# Sheet1.net
KiCad netlist of a schematic drawn in Altium Designer
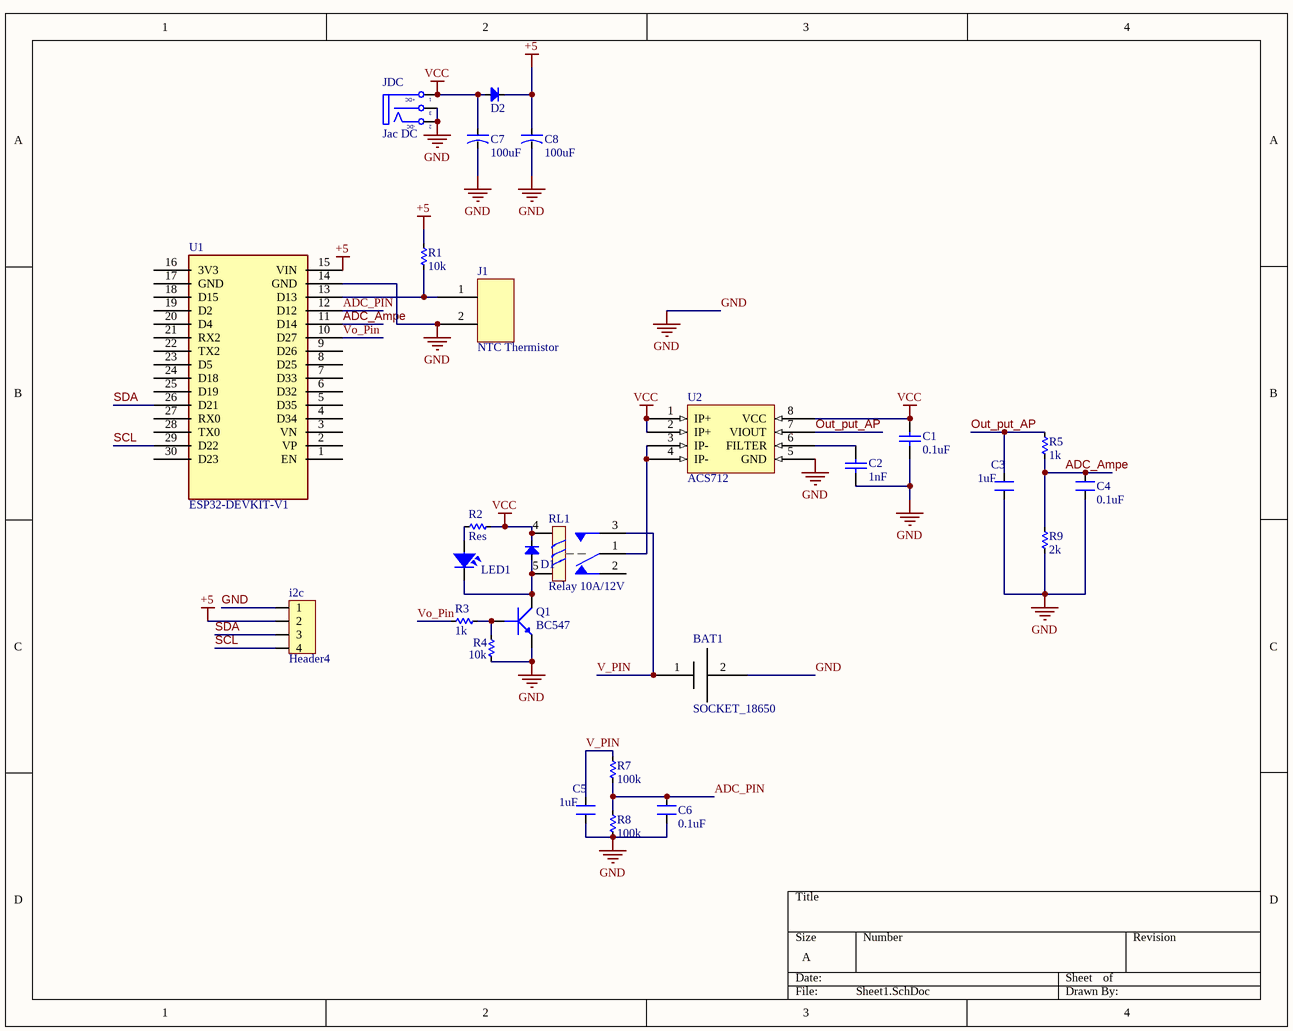
[diagram p0: Sheet1.SchDoc]

(export (version "E")
  (design (tool "Eeschema 10.0.6"))
  (components
    (comp (ref "BAT1")
      (value "SOCKET_18650")
      (footprint "SOCKET_18650_1PIN")
      (libsource (lib "Integrated_Library1") (part "SOCKET_18650_1PIN"))
    )
    (comp (ref "C1")
      (value "0.1uF")
      (footprint "CAPC_0603_N")
      (description "CAP CER 0.1UF 50V X7R 0603")
      (fields (field (name "PARTNUMBER") "C0603X7R104K500NT") (field (name "CREATOR") "ThangND"))
      (libsource (lib "MKP_lib") (part "CAP"))
    )
    (comp (ref "C2")
      (value "1nF")
      (footprint "CAPC_0603_N")
      (description "CAP CER 0.1UF 50V X7R 0603")
      (fields (field (name "PARTNUMBER") "C0603X7R104K500NT") (field (name "CREATOR") "ThangND"))
      (libsource (lib "MKP_lib") (part "CAP"))
    )
    (comp (ref "C3")
      (value "1uF")
      (footprint "CN1")
      (description "Cap np  1pF - 472pF")
      (libsource (lib "syhaunguyen") (part "CN1"))
    )
    (comp (ref "C4")
      (value "0.1uF")
      (footprint "CN1")
      (description "Cap np  1pF - 472pF")
      (libsource (lib "syhaunguyen") (part "CN1"))
    )
    (comp (ref "C5")
      (value "1uF")
      (footprint "CN1")
      (description "Cap np  1pF - 472pF")
      (libsource (lib "syhaunguyen") (part "CN1"))
    )
    (comp (ref "C6")
      (value "0.1uF")
      (footprint "CN1")
      (description "Cap np  1pF - 472pF")
      (libsource (lib "syhaunguyen") (part "CN1"))
    )
    (comp (ref "C7")
      (value "100uF")
      (footprint "CA-ALU-6.3")
      (description "Capacitor (Semiconductor SIM Model)")
      (fields (field (name "PUBLISHER") "Altium Limited"))
      (libsource (lib "LIBRARY") (part "CN-ALU-DIP"))
    )
    (comp (ref "C8")
      (value "100uF")
      (footprint "CA-ALU-6.3")
      (description "Capacitor (Semiconductor SIM Model)")
      (fields (field (name "PUBLISHER") "Altium Limited"))
      (libsource (lib "LIBRARY") (part "CN-ALU-DIP"))
    )
    (comp (ref "D1")
      (value "Diode")
      (footprint "DIO-1A")
      (description "Default Diode")
      (fields (field (name "PUBLISHER") "Altium Limited"))
      (libsource (lib "LIBRARY") (part "Diode"))
    )
    (comp (ref "D2")
      (value "Diode")
      (footprint "DIO-1A")
      (description "Default Diode")
      (fields (field (name "PUBLISHER") "Altium Limited"))
      (libsource (lib "LIBRARY") (part "Diode"))
    )
    (comp (ref "i2c")
      (value "Header4")
      (footprint "Header4")
      (description "Header IDC, 4 x 1 Pin Vertical 2.54mm Pitch (Non-Boxed, Male)")
      (fields
        (field (name "MANUFACTURER") "Würth Elektronik eiSos GmbH")
        (field (name "PARTNO") "613002143121")
        (field (name "CREATED BY") "Karrer Zheng")
      )
      (libsource (lib "LIBRARY") (part "Header4"))
    )
    (comp (ref "J1")
      (value "NTC Thermistor")
      (footprint "NTC Thermistor")
      (libsource (lib "Hainv-makipos") (part "NTC Thermistor"))
    )
    (comp (ref "JDC")
      (value "Jac DC")
      (footprint "DC0")
      (description "Jac DC input")
      (libsource (lib "LIBRARY") (part "DCIN"))
    )
    (comp (ref "LED1")
      (value "LED")
      (footprint "LED-5-Green")
      (description "LED Single colour Green and Red")
      (libsource (lib "LIBRARY") (part "LED"))
    )
    (comp (ref "Q1")
      (value "BC547")
      (footprint "TO-92")
      (description "Transistors - BJT NPN 45V 100mA")
      (libsource (lib "MHieuLib") (part "BC547"))
    )
    (comp (ref "R1")
      (value "10k")
      (footprint "RES-1/4W")
      (description "Res")
      (fields
        (field (name "MANUFACTURER") "Generic Components")
        (field (name "PUBLISHER") "Altium Hobart Technology Centre")
      )
      (libsource (lib "LIBRARY") (part "Res"))
    )
    (comp (ref "R2")
      (value "Res")
      (footprint "RES-1/4W")
      (fields
        (field (name "MANUFACTURER") "Generic Components")
        (field (name "PUBLISHER") "Altium Hobart Technology Centre")
      )
      (libsource (lib "LIBRARY") (part "Res"))
    )
    (comp (ref "R3")
      (value "1k")
      (footprint "RES-1/4W")
      (description "Res")
      (fields
        (field (name "MANUFACTURER") "Generic Components")
        (field (name "PUBLISHER") "Altium Hobart Technology Centre")
      )
      (libsource (lib "LIBRARY") (part "Res"))
    )
    (comp (ref "R4")
      (value "10k")
      (footprint "RES-1/4W")
      (description "Res")
      (fields
        (field (name "MANUFACTURER") "Generic Components")
        (field (name "PUBLISHER") "Altium Hobart Technology Centre")
      )
      (libsource (lib "LIBRARY") (part "Res"))
    )
    (comp (ref "R5")
      (value "1k")
      (footprint "RES-1/4W")
      (description "Res")
      (fields
        (field (name "MANUFACTURER") "Generic Components")
        (field (name "PUBLISHER") "Altium Hobart Technology Centre")
      )
      (libsource (lib "LIBRARY") (part "Res"))
    )
    (comp (ref "R7")
      (value "100k")
      (footprint "RES-1/4W")
      (description "Res")
      (fields
        (field (name "MANUFACTURER") "Generic Components")
        (field (name "PUBLISHER") "Altium Hobart Technology Centre")
      )
      (libsource (lib "LIBRARY") (part "Res"))
    )
    (comp (ref "R8")
      (value "100k")
      (footprint "RES-1/4W")
      (description "Res")
      (fields
        (field (name "MANUFACTURER") "Generic Components")
        (field (name "PUBLISHER") "Altium Hobart Technology Centre")
      )
      (libsource (lib "LIBRARY") (part "Res"))
    )
    (comp (ref "R9")
      (value "2k")
      (footprint "RES-1/4W")
      (description "Res")
      (fields
        (field (name "MANUFACTURER") "Generic Components")
        (field (name "PUBLISHER") "Altium Hobart Technology Centre")
      )
      (libsource (lib "LIBRARY") (part "Res"))
    )
    (comp (ref "RL1")
      (value "Relay 10A/12V")
      (footprint "RELAY 5")
      (description "Relay SPDT,10A - 12VDC 5 Pin")
      (libsource (lib "LIBRARY") (part "Relay 5"))
    )
    (comp (ref "U1")
      (value "ESP32-DEVKIT-V1")
      (footprint "ESP32-DEVKIT-V1")
      (description "ESP32-DEVKIT-V1 30Pin")
      (libsource (lib "Library") (part "ESP32-DEVKIT-V1"))
    )
    (comp (ref "U2")
      (value "ACS712")
      (footprint "ACS712")
      (description "5A SOIC-8 Current Sensors ROHS")
      (libsource (lib "Hainv-makipos") (part "ACS712"))
    )
  )
  (nets
    (net (code "1") (name "+5") (class "Default")
      (node (ref "C8") (pin "1") (pinfunction "1_1") (pintype "passive"))
      (node (ref "D2") (pin "2") (pinfunction "K_2") (pintype "passive"))
      (node (ref "R1") (pin "2") (pinfunction "2_2") (pintype "passive"))
      (node (ref "U1") (pin "15") (pinfunction "VIN_15") (pintype "passive"))
      (node (ref "i2c") (pin "2") (pinfunction "2_2") (pintype "passive"))
    )
    (net (code "2") (name "/ADC_Ampe") (class "Default")
      (node (ref "C4") (pin "2") (pinfunction "2_2") (pintype "passive"))
      (node (ref "R5") (pin "1") (pinfunction "1_1") (pintype "passive"))
      (node (ref "R9") (pin "2") (pinfunction "2_2") (pintype "passive"))
      (node (ref "U1") (pin "11") (pinfunction "D14_11") (pintype "passive"))
    )
    (net (code "3") (name "/ADC_PIN") (class "Default")
      (node (ref "C6") (pin "2") (pinfunction "2_2") (pintype "passive"))
      (node (ref "R7") (pin "1") (pinfunction "1_1") (pintype "passive"))
      (node (ref "R8") (pin "2") (pinfunction "2_2") (pintype "passive"))
      (node (ref "U1") (pin "12") (pinfunction "D12_12") (pintype "passive"))
    )
    (net (code "4") (name "/Out_put_AP") (class "Default")
      (node (ref "C3") (pin "2") (pinfunction "2_2") (pintype "passive"))
      (node (ref "R5") (pin "2") (pinfunction "2_2") (pintype "passive"))
      (node (ref "U2") (pin "7") (pinfunction "VIOUT_7") (pintype "input"))
    )
    (net (code "5") (name "/SCL") (class "Default")
      (node (ref "U1") (pin "29") (pinfunction "D22_29") (pintype "passive"))
      (node (ref "i2c") (pin "4") (pinfunction "4_4") (pintype "passive"))
    )
    (net (code "6") (name "/SDA") (class "Default")
      (node (ref "U1") (pin "26") (pinfunction "D21_26") (pintype "passive"))
      (node (ref "i2c") (pin "3") (pinfunction "3_3") (pintype "passive"))
    )
    (net (code "7") (name "/V_PIN") (class "Default")
      (node (ref "BAT1") (pin "1") (pinfunction "VCC_1") (pintype "passive"))
      (node (ref "C5") (pin "2") (pinfunction "2_2") (pintype "passive"))
      (node (ref "R7") (pin "2") (pinfunction "2_2") (pintype "passive"))
      (node (ref "RL1") (pin "3") (pinfunction "3_3") (pintype "passive"))
    )
    (net (code "8") (name "/Vo_Pin") (class "Default")
      (node (ref "R3") (pin "2") (pinfunction "2_2") (pintype "passive"))
      (node (ref "U1") (pin "10") (pinfunction "D27_10") (pintype "passive"))
    )
    (net (code "9") (name "GND") (class "Default")
      (node (ref "BAT1") (pin "2") (pinfunction "GND_2") (pintype "passive"))
      (node (ref "C1") (pin "1") (pinfunction "1_1") (pintype "passive"))
      (node (ref "C2") (pin "1") (pinfunction "1_1") (pintype "passive"))
      (node (ref "C3") (pin "1") (pinfunction "1_1") (pintype "passive"))
      (node (ref "C4") (pin "1") (pinfunction "1_1") (pintype "passive"))
      (node (ref "C5") (pin "1") (pinfunction "1_1") (pintype "passive"))
      (node (ref "C6") (pin "1") (pinfunction "1_1") (pintype "passive"))
      (node (ref "C7") (pin "2") (pinfunction "2_2") (pintype "passive"))
      (node (ref "C8") (pin "2") (pinfunction "2_2") (pintype "passive"))
      (node (ref "J1") (pin "2") (pintype "passive"))
      (node (ref "JDC") (pin "2") (pinfunction "TN_2") (pintype "passive"))
      (node (ref "JDC") (pin "3") (pinfunction "S_3") (pintype "power_in"))
      (node (ref "Q1") (pin "3") (pinfunction "E_3") (pintype "passive"))
      (node (ref "R4") (pin "1") (pinfunction "1_1") (pintype "passive"))
      (node (ref "R8") (pin "1") (pinfunction "1_1") (pintype "passive"))
      (node (ref "R9") (pin "1") (pinfunction "1_1") (pintype "passive"))
      (node (ref "U1") (pin "14") (pinfunction "GND_14") (pintype "passive"))
      (node (ref "U2") (pin "5") (pinfunction "GND_5") (pintype "input"))
      (node (ref "i2c") (pin "1") (pinfunction "1_1") (pintype "passive"))
    )
    (net (code "10") (name "Net-(D1-A)") (class "Default")
      (node (ref "D1") (pin "1") (pinfunction "A_1") (pintype "passive"))
      (node (ref "LED1") (pin "2") (pinfunction "2_2") (pintype "passive"))
      (node (ref "Q1") (pin "1") (pinfunction "C_1") (pintype "passive"))
      (node (ref "RL1") (pin "5") (pinfunction "5_5") (pintype "passive"))
    )
    (net (code "11") (name "Net-(LED1-Pad1)") (class "Default")
      (node (ref "LED1") (pin "1") (pinfunction "1_1") (pintype "passive"))
      (node (ref "R2") (pin "1") (pinfunction "1_1") (pintype "passive"))
    )
    (net (code "12") (name "Net-(Q1-B)") (class "Default")
      (node (ref "Q1") (pin "2") (pinfunction "B_2") (pintype "passive"))
      (node (ref "R3") (pin "1") (pinfunction "1_1") (pintype "passive"))
      (node (ref "R4") (pin "2") (pinfunction "2_2") (pintype "passive"))
    )
    (net (code "13") (name "Net-(RL1-Pad1)") (class "Default")
      (node (ref "RL1") (pin "1") (pinfunction "1_1") (pintype "passive"))
      (node (ref "U2") (pin "3") (pinfunction "IP-_3") (pintype "input"))
      (node (ref "U2") (pin "4") (pinfunction "IP-_4") (pintype "input"))
    )
    (net (code "14") (name "Net-(U1-D13)") (class "Default")
      (node (ref "J1") (pin "1") (pintype "passive"))
      (node (ref "R1") (pin "1") (pinfunction "1_1") (pintype "passive"))
      (node (ref "U1") (pin "13") (pinfunction "D13_13") (pintype "passive"))
    )
    (net (code "15") (name "Net-(U2-FILTER)") (class "Default")
      (node (ref "C2") (pin "2") (pinfunction "2_2") (pintype "passive"))
      (node (ref "U2") (pin "6") (pinfunction "FILTER_6") (pintype "input"))
    )
    (net (code "16") (name "VCC") (class "Default")
      (node (ref "C1") (pin "2") (pinfunction "2_2") (pintype "passive"))
      (node (ref "C7") (pin "1") (pinfunction "1_1") (pintype "passive"))
      (node (ref "D1") (pin "2") (pinfunction "K_2") (pintype "passive"))
      (node (ref "D2") (pin "1") (pinfunction "A_1") (pintype "passive"))
      (node (ref "JDC") (pin "1") (pinfunction "T_1") (pintype "passive"))
      (node (ref "R2") (pin "2") (pinfunction "2_2") (pintype "passive"))
      (node (ref "RL1") (pin "4") (pinfunction "4_4") (pintype "passive"))
      (node (ref "U2") (pin "1") (pinfunction "IP+_1") (pintype "input"))
      (node (ref "U2") (pin "2") (pinfunction "IP+_2") (pintype "input"))
      (node (ref "U2") (pin "8") (pinfunction "VCC_8") (pintype "input"))
    )
    (net (code "17") (name "unconnected-(RL1-Pad2)") (class "Default")
      (node (ref "RL1") (pin "2") (pinfunction "2_2") (pintype "passive"))
    )
    (net (code "18") (name "unconnected-(U1-3V3-Pad16)") (class "Default")
      (node (ref "U1") (pin "16") (pinfunction "3V3_16") (pintype "passive"))
    )
    (net (code "19") (name "unconnected-(U1-D2-Pad19)") (class "Default")
      (node (ref "U1") (pin "19") (pinfunction "D2_19") (pintype "passive"))
    )
    (net (code "20") (name "unconnected-(U1-D4-Pad20)") (class "Default")
      (node (ref "U1") (pin "20") (pinfunction "D4_20") (pintype "passive"))
    )
    (net (code "21") (name "unconnected-(U1-D5-Pad23)") (class "Default")
      (node (ref "U1") (pin "23") (pinfunction "D5_23") (pintype "passive"))
    )
    (net (code "22") (name "unconnected-(U1-D15-Pad18)") (class "Default")
      (node (ref "U1") (pin "18") (pinfunction "D15_18") (pintype "passive"))
    )
    (net (code "23") (name "unconnected-(U1-D18-Pad24)") (class "Default")
      (node (ref "U1") (pin "24") (pinfunction "D18_24") (pintype "passive"))
    )
    (net (code "24") (name "unconnected-(U1-D19-Pad25)") (class "Default")
      (node (ref "U1") (pin "25") (pinfunction "D19_25") (pintype "passive"))
    )
    (net (code "25") (name "unconnected-(U1-D23-Pad30)") (class "Default")
      (node (ref "U1") (pin "30") (pinfunction "D23_30") (pintype "passive"))
    )
    (net (code "26") (name "unconnected-(U1-D25-Pad8)") (class "Default")
      (node (ref "U1") (pin "8") (pinfunction "D25_8") (pintype "passive"))
    )
    (net (code "27") (name "unconnected-(U1-D26-Pad9)") (class "Default")
      (node (ref "U1") (pin "9") (pinfunction "D26_9") (pintype "passive"))
    )
    (net (code "28") (name "unconnected-(U1-D32-Pad6)") (class "Default")
      (node (ref "U1") (pin "6") (pinfunction "D32_6") (pintype "passive"))
    )
    (net (code "29") (name "unconnected-(U1-D33-Pad7)") (class "Default")
      (node (ref "U1") (pin "7") (pinfunction "D33_7") (pintype "passive"))
    )
    (net (code "30") (name "unconnected-(U1-D34-Pad4)") (class "Default")
      (node (ref "U1") (pin "4") (pinfunction "D34_4") (pintype "passive"))
    )
    (net (code "31") (name "unconnected-(U1-D35-Pad5)") (class "Default")
      (node (ref "U1") (pin "5") (pinfunction "D35_5") (pintype "passive"))
    )
    (net (code "32") (name "unconnected-(U1-EN-Pad1)") (class "Default")
      (node (ref "U1") (pin "1") (pinfunction "EN_1") (pintype "passive"))
    )
    (net (code "33") (name "unconnected-(U1-GND-Pad17)") (class "Default")
      (node (ref "U1") (pin "17") (pinfunction "GND_17") (pintype "passive"))
    )
    (net (code "34") (name "unconnected-(U1-RX0-Pad27)") (class "Default")
      (node (ref "U1") (pin "27") (pinfunction "RX0_27") (pintype "passive"))
    )
    (net (code "35") (name "unconnected-(U1-RX2-Pad21)") (class "Default")
      (node (ref "U1") (pin "21") (pinfunction "RX2_21") (pintype "passive"))
    )
    (net (code "36") (name "unconnected-(U1-TX0-Pad28)") (class "Default")
      (node (ref "U1") (pin "28") (pinfunction "TX0_28") (pintype "passive"))
    )
    (net (code "37") (name "unconnected-(U1-TX2-Pad22)") (class "Default")
      (node (ref "U1") (pin "22") (pinfunction "TX2_22") (pintype "passive"))
    )
    (net (code "38") (name "unconnected-(U1-VN-Pad3)") (class "Default")
      (node (ref "U1") (pin "3") (pinfunction "VN_3") (pintype "passive"))
    )
    (net (code "39") (name "unconnected-(U1-VP-Pad2)") (class "Default")
      (node (ref "U1") (pin "2") (pinfunction "VP_2") (pintype "passive"))
    )
  )
)
